# AT24-Timer-NEW.net
KiCad netlist of a schematic drawn in EAGLE
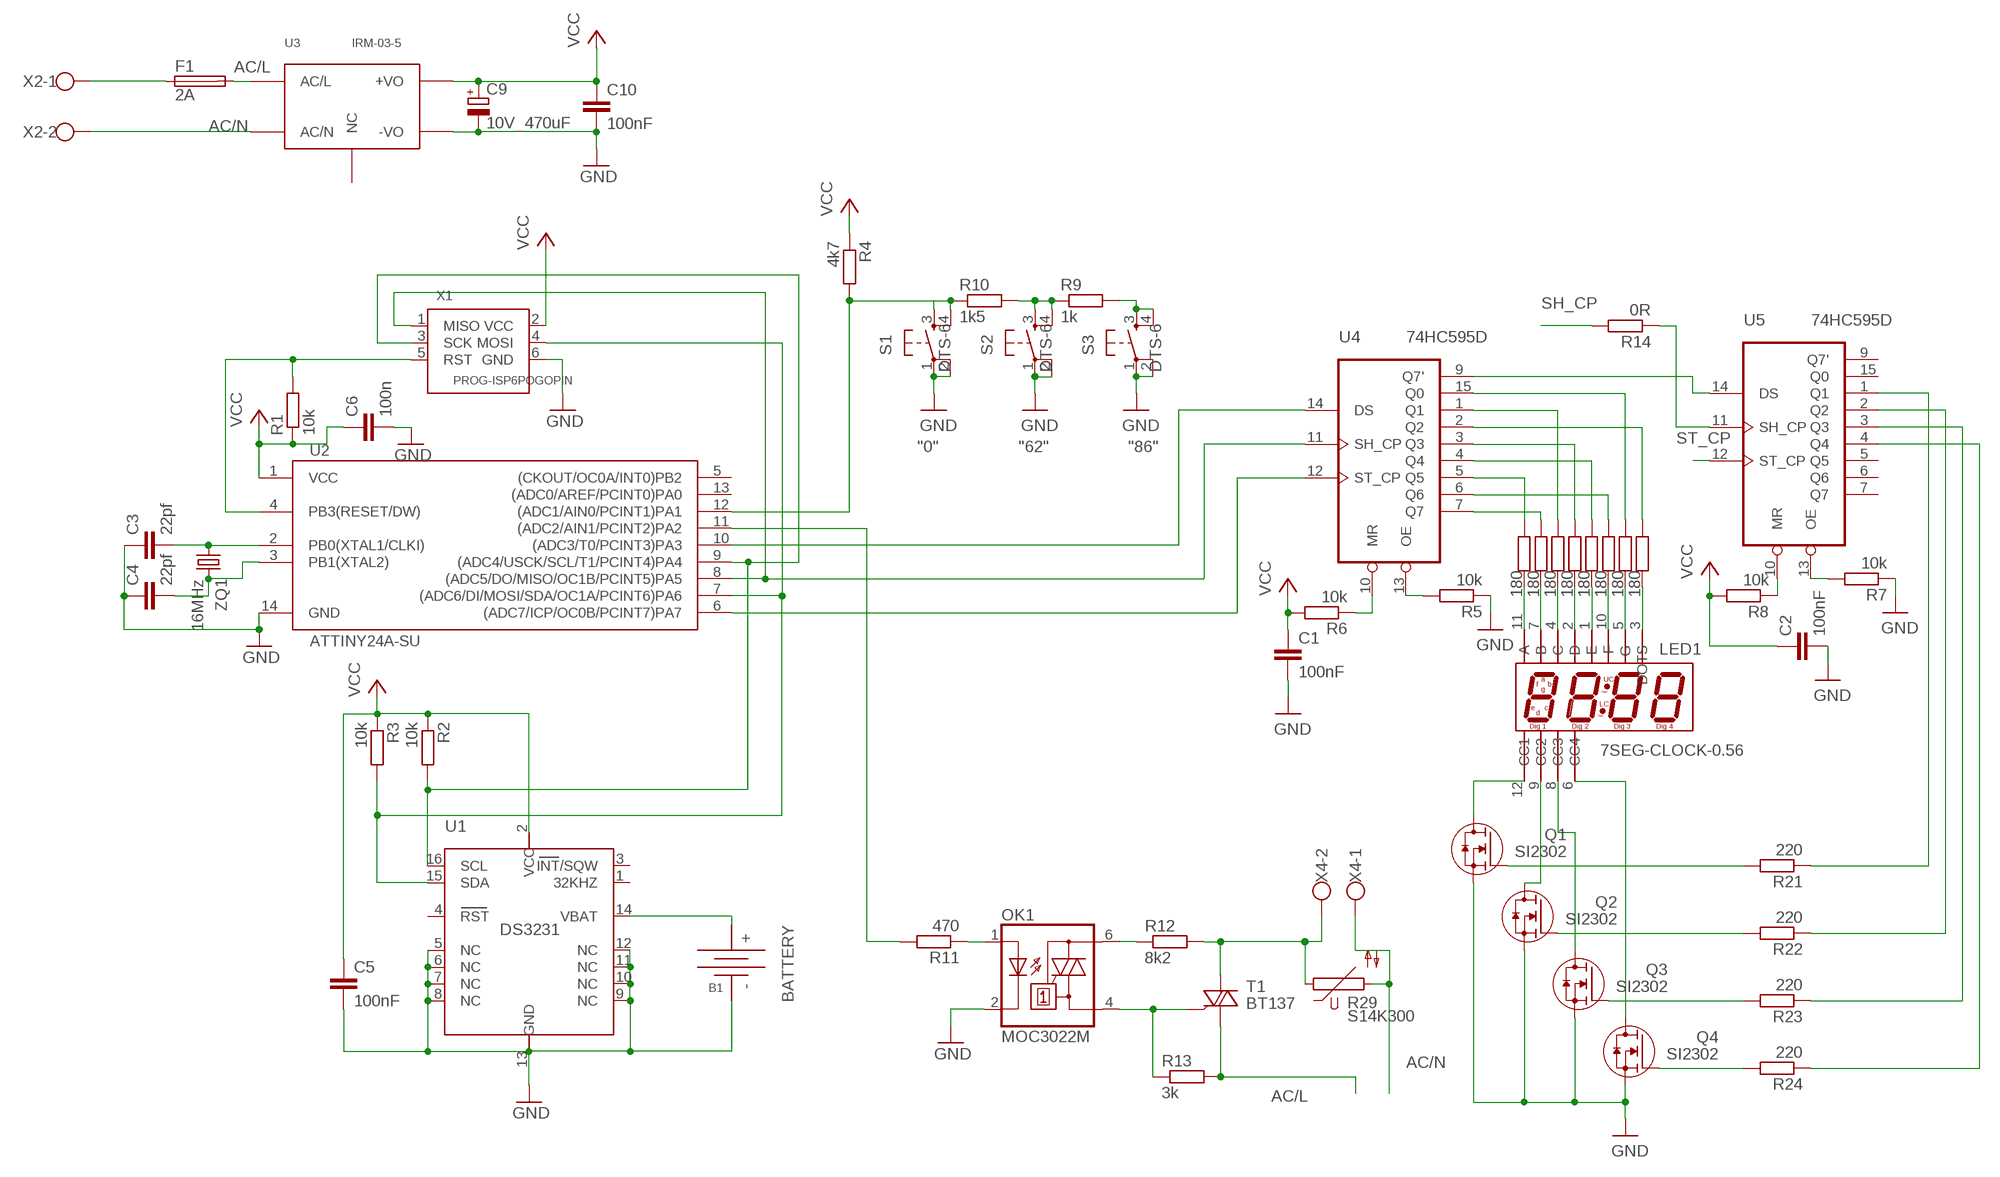
[diagram p0: schematic, sheet 1]

(export (version "E")
  (design (tool "Eeschema 10.0.6"))
  (components
    (comp (ref "B1")
      (value "BATTERY")
      (footprint "eagle-import:BTH2032-3")
      (libsource (lib "eagle-import") (part "BATTERY"))
    )
    (comp (ref "C1")
      (value "100nF")
      (footprint "eagle-import:C0603")
      (libsource (lib "eagle-import") (part "C-EUC0603"))
    )
    (comp (ref "C2")
      (value "100nF")
      (footprint "eagle-import:C0603")
      (libsource (lib "eagle-import") (part "C-EUC0603"))
    )
    (comp (ref "C3")
      (value "22pf")
      (footprint "eagle-import:C0603")
      (libsource (lib "eagle-import") (part "C-EUC0603"))
    )
    (comp (ref "C4")
      (value "22pf")
      (footprint "eagle-import:C0603")
      (libsource (lib "eagle-import") (part "C-EUC0603"))
    )
    (comp (ref "C5")
      (value "100nF")
      (footprint "eagle-import:C0603")
      (libsource (lib "eagle-import") (part "C-EUC0603"))
    )
    (comp (ref "C6")
      (value "100n")
      (footprint "eagle-import:C0603")
      (libsource (lib "eagle-import") (part "C-EUC0603"))
    )
    (comp (ref "C9")
      (value "10V_470uF")
      (footprint "eagle-import:D_7343-31W")
      (libsource (lib "eagle-import") (part "CPOL-EUD/7343-31W"))
    )
    (comp (ref "C10")
      (value "100nF")
      (footprint "eagle-import:C0805K")
      (libsource (lib "eagle-import") (part "C-EUC0805K"))
    )
    (comp (ref "F1")
      (value "2A")
      (footprint "eagle-import:SH22,5A")
      (fields (field (name "MPN") "0031.7701.11"))
      (libsource (lib "eagle-import") (part "SH22,5A"))
    )
    (comp (ref "LED1")
      (value "7SEG-CLOCK-0.56")
      (footprint "eagle-import:7SEG_4DIG_0.56")
      (libsource (lib "eagle-import") (part "7SEG-CLOCK-0.56"))
    )
    (comp (ref "OK1")
      (value "MOC3022M")
      (footprint "eagle-import:DIL06")
      (fields (field (name "MF") "FAIRCHILD SEMICONDUCTOR") (field (name "MPN") "MOC3022-M"))
      (libsource (lib "eagle-import") (part "MOC30M22"))
    )
    (comp (ref "Q1")
      (value "SI2302")
      (footprint "eagle-import:SOT-23-GSD")
      (libsource (lib "eagle-import") (part "SI2302"))
    )
    (comp (ref "Q2")
      (value "SI2302")
      (footprint "eagle-import:SOT-23-GSD")
      (libsource (lib "eagle-import") (part "SI2302"))
    )
    (comp (ref "Q3")
      (value "SI2302")
      (footprint "eagle-import:SOT-23-GSD")
      (libsource (lib "eagle-import") (part "SI2302"))
    )
    (comp (ref "Q4")
      (value "SI2302")
      (footprint "eagle-import:SOT-23-GSD")
      (libsource (lib "eagle-import") (part "SI2302"))
    )
    (comp (ref "R1")
      (value "10k")
      (footprint "eagle-import:R0805")
      (libsource (lib "eagle-import") (part "R-EU_R0805"))
    )
    (comp (ref "R2")
      (value "10k")
      (footprint "eagle-import:R0805")
      (libsource (lib "eagle-import") (part "R-EU_R0805"))
    )
    (comp (ref "R3")
      (value "10k")
      (footprint "eagle-import:R0805")
      (libsource (lib "eagle-import") (part "R-EU_R0805"))
    )
    (comp (ref "R4")
      (value "4k7")
      (footprint "eagle-import:R0805")
      (libsource (lib "eagle-import") (part "R-EU_R0805"))
    )
    (comp (ref "R5")
      (value "10k")
      (footprint "eagle-import:R0805")
      (libsource (lib "eagle-import") (part "R-EU_R0805"))
    )
    (comp (ref "R6")
      (value "10k")
      (footprint "eagle-import:R0805")
      (libsource (lib "eagle-import") (part "R-EU_R0805"))
    )
    (comp (ref "R7")
      (value "10k")
      (footprint "eagle-import:0805R")
      (libsource (lib "eagle-import") (part "R0805"))
    )
    (comp (ref "R8")
      (value "10k")
      (footprint "eagle-import:R0805")
      (libsource (lib "eagle-import") (part "R-EU_R0805"))
    )
    (comp (ref "R9")
      (value "1k")
      (footprint "eagle-import:R0805")
      (libsource (lib "eagle-import") (part "R-EU_R0805"))
    )
    (comp (ref "R10")
      (value "1k5")
      (footprint "eagle-import:R0805")
      (libsource (lib "eagle-import") (part "R-EU_R0805"))
    )
    (comp (ref "R11")
      (value "470")
      (footprint "eagle-import:R0805")
      (libsource (lib "eagle-import") (part "R-EU_R0805"))
    )
    (comp (ref "R12")
      (value "8k2")
      (footprint "eagle-import:0207_7")
      (libsource (lib "eagle-import") (part "R-EU_0207/7"))
    )
    (comp (ref "R13")
      (value "3k")
      (footprint "eagle-import:0207_7")
      (libsource (lib "eagle-import") (part "R-EU_0207/7"))
    )
    (comp (ref "R14")
      (value "0R")
      (footprint "eagle-import:0805R")
      (libsource (lib "eagle-import") (part "R0805"))
    )
    (comp (ref "R17")
      (value "180")
      (footprint "eagle-import:R0805")
      (libsource (lib "eagle-import") (part "R-EU_R0805"))
    )
    (comp (ref "R18")
      (value "180")
      (footprint "eagle-import:R0805")
      (libsource (lib "eagle-import") (part "R-EU_R0805"))
    )
    (comp (ref "R19")
      (value "180")
      (footprint "eagle-import:R0805")
      (libsource (lib "eagle-import") (part "R-EU_R0805"))
    )
    (comp (ref "R20")
      (value "180")
      (footprint "eagle-import:R0805")
      (libsource (lib "eagle-import") (part "R-EU_R0805"))
    )
    (comp (ref "R21")
      (value "220")
      (footprint "eagle-import:R0805")
      (libsource (lib "eagle-import") (part "R-EU_R0805"))
    )
    (comp (ref "R22")
      (value "220")
      (footprint "eagle-import:R0805")
      (libsource (lib "eagle-import") (part "R-EU_R0805"))
    )
    (comp (ref "R23")
      (value "220")
      (footprint "eagle-import:R0805")
      (libsource (lib "eagle-import") (part "R-EU_R0805"))
    )
    (comp (ref "R24")
      (value "220")
      (footprint "eagle-import:R0805")
      (libsource (lib "eagle-import") (part "R-EU_R0805"))
    )
    (comp (ref "R25")
      (value "180")
      (footprint "eagle-import:R0805")
      (libsource (lib "eagle-import") (part "R-EU_R0805"))
    )
    (comp (ref "R26")
      (value "180")
      (footprint "eagle-import:R0805")
      (libsource (lib "eagle-import") (part "R-EU_R0805"))
    )
    (comp (ref "R27")
      (value "180")
      (footprint "eagle-import:R0805")
      (libsource (lib "eagle-import") (part "R-EU_R0805"))
    )
    (comp (ref "R28")
      (value "180")
      (footprint "eagle-import:R0805")
      (libsource (lib "eagle-import") (part "R-EU_R0805"))
    )
    (comp (ref "R29")
      (value "S14K300")
      (footprint "eagle-import:S14K300")
      (libsource (lib "eagle-import") (part "S14K300"))
    )
    (comp (ref "S1")
      (value "DTS-6")
      (footprint "eagle-import:DTS-6")
      (libsource (lib "eagle-import") (part "DTS-6"))
    )
    (comp (ref "S2")
      (value "DTS-6")
      (footprint "eagle-import:DTS-6")
      (libsource (lib "eagle-import") (part "DTS-6"))
    )
    (comp (ref "S3")
      (value "DTS-6")
      (footprint "eagle-import:DTS-6")
      (libsource (lib "eagle-import") (part "DTS-6"))
    )
    (comp (ref "T1")
      (value "BT137")
      (footprint "eagle-import:TO220AB")
      (libsource (lib "eagle-import") (part "BT136"))
    )
    (comp (ref "U1")
      (value "DS3231")
      (footprint "eagle-import:SO16L")
      (libsource (lib "eagle-import") (part "DS3231"))
    )
    (comp (ref "U2")
      (value "ATTINY24A-SU")
      (footprint "eagle-import:SO14")
      (libsource (lib "eagle-import") (part "ATTINY24A-SU"))
    )
    (comp (ref "U3")
      (value "IRM-03-5")
      (footprint "eagle-import:IRM-03-_")
      (libsource (lib "eagle-import") (part "IRM-03-5"))
    )
    (comp (ref "U4")
      (value "74HC595D")
      (footprint "eagle-import:SO16")
      (libsource (lib "eagle-import") (part "74595DHC"))
    )
    (comp (ref "U5")
      (value "74HC595D")
      (footprint "eagle-import:SO16")
      (libsource (lib "eagle-import") (part "74595DHC"))
    )
    (comp (ref "X1")
      (value "PROG-ISP6POGOPIN")
      (footprint "eagle-import:PROG_POGOPIN")
      (libsource (lib "eagle-import") (part "PROG-ISP6POGOPIN"))
    )
    (comp (ref "X2")
      (value "W237-102")
      (footprint "eagle-import:W237-102")
      (fields (field (name "MPN") "237-102"))
      (libsource (lib "eagle-import") (part "W237-102"))
    )
    (comp (ref "X4")
      (value "W237-102")
      (footprint "eagle-import:W237-102")
      (fields (field (name "MPN") "237-102"))
      (libsource (lib "eagle-import") (part "W237-102"))
    )
    (comp (ref "ZQ1")
      (value "16MHz")
      (footprint "eagle-import:HC49_S")
      (libsource (lib "eagle-import") (part "CRYSTALHC49S"))
    )
  )
  (nets
    (net (code "1") (name "/AC{slash}L") (class "Default")
      (node (ref "F1") (pin "2") (pinfunction "2_2") (pintype "passive"))
      (node (ref "R13") (pin "2") (pinfunction "2_2") (pintype "passive"))
      (node (ref "T1") (pin "1") (pinfunction "A1_1") (pintype "passive"))
      (node (ref "U3") (pin "P$1") (pinfunction "AC/L_P$1") (pintype "power_in"))
    )
    (net (code "2") (name "/AC{slash}N") (class "Default")
      (node (ref "R29") (pin "2") (pinfunction "2_2") (pintype "passive"))
      (node (ref "U3") (pin "P$2") (pinfunction "AC/N_P$2") (pintype "power_in"))
      (node (ref "X2") (pin "2") (pinfunction "KL_2") (pintype "passive"))
      (node (ref "X4") (pin "1") (pinfunction "KL_1") (pintype "passive"))
    )
    (net (code "3") (name "/NC") (class "Default")
      (node (ref "U3") (pin "P$3") (pinfunction "NC_P$3") (pintype "power_in"))
    )
    (net (code "4") (name "/SH_CP") (class "Default")
      (node (ref "R14") (pin "2") (pinfunction "2_2") (pintype "passive"))
      (node (ref "U2") (pin "8") (pinfunction "(ADC5/DO/MISO/OC1B/PCINT5)PA5_8") (pintype "bidirectional"))
      (node (ref "U4") (pin "11") (pinfunction "SH_CP_11") (pintype "input"))
      (node (ref "X1") (pin "1") (pinfunction "MISO_1") (pintype "bidirectional"))
    )
    (net (code "5") (name "/ST_CP") (class "Default")
      (node (ref "U2") (pin "6") (pinfunction "(ADC7/ICP/OC0B/PCINT7)PA7_6") (pintype "bidirectional"))
      (node (ref "U4") (pin "12") (pinfunction "ST_CP_12") (pintype "input"))
      (node (ref "U5") (pin "12") (pinfunction "ST_CP_12") (pintype "input"))
    )
    (net (code "6") (name "GND") (class "Default")
      (node (ref "B1") (pin "-") (pinfunction "-_-") (pintype "power_in"))
      (node (ref "C1") (pin "2") (pinfunction "2_2") (pintype "passive"))
      (node (ref "C10") (pin "2") (pinfunction "2_2") (pintype "passive"))
      (node (ref "C2") (pin "2") (pinfunction "2_2") (pintype "passive"))
      (node (ref "C3") (pin "1") (pinfunction "1_1") (pintype "passive"))
      (node (ref "C4") (pin "1") (pinfunction "1_1") (pintype "passive"))
      (node (ref "C5") (pin "2") (pinfunction "2_2") (pintype "passive"))
      (node (ref "C6") (pin "2") (pinfunction "2_2") (pintype "passive"))
      (node (ref "C9") (pin "-") (pinfunction "-_-") (pintype "passive"))
      (node (ref "OK1") (pin "2") (pinfunction "C_2") (pintype "passive"))
      (node (ref "Q1") (pin "S") (pinfunction "S_S") (pintype "passive"))
      (node (ref "Q2") (pin "S") (pinfunction "S_S") (pintype "passive"))
      (node (ref "Q3") (pin "S") (pinfunction "S_S") (pintype "passive"))
      (node (ref "Q4") (pin "S") (pinfunction "S_S") (pintype "passive"))
      (node (ref "R5") (pin "1") (pinfunction "1_1") (pintype "passive"))
      (node (ref "R7") (pin "1") (pinfunction "1_1") (pintype "passive"))
      (node (ref "S1") (pin "1") (pinfunction "1_1") (pintype "passive"))
      (node (ref "S1") (pin "2") (pinfunction "2_2") (pintype "passive"))
      (node (ref "S2") (pin "1") (pinfunction "1_1") (pintype "passive"))
      (node (ref "S2") (pin "2") (pinfunction "2_2") (pintype "passive"))
      (node (ref "S3") (pin "1") (pinfunction "1_1") (pintype "passive"))
      (node (ref "S3") (pin "2") (pinfunction "2_2") (pintype "passive"))
      (node (ref "U1") (pin "10") (pinfunction "NC_10") (pintype "bidirectional"))
      (node (ref "U1") (pin "11") (pinfunction "NC_11") (pintype "bidirectional"))
      (node (ref "U1") (pin "12") (pinfunction "NC_12") (pintype "bidirectional"))
      (node (ref "U1") (pin "13") (pinfunction "GND_13") (pintype "power_in"))
      (node (ref "U1") (pin "5") (pinfunction "NC_5") (pintype "bidirectional"))
      (node (ref "U1") (pin "6") (pinfunction "NC_6") (pintype "bidirectional"))
      (node (ref "U1") (pin "7") (pinfunction "NC_7") (pintype "bidirectional"))
      (node (ref "U1") (pin "8") (pinfunction "NC_8") (pintype "bidirectional"))
      (node (ref "U1") (pin "9") (pinfunction "NC_9") (pintype "bidirectional"))
      (node (ref "U2") (pin "14") (pinfunction "GND_14") (pintype "power_in"))
      (node (ref "U3") (pin "P$4") (pinfunction "-VO_P$4") (pintype "power_in"))
      (node (ref "X1") (pin "6") (pinfunction "GND_6") (pintype "power_in"))
    )
    (net (code "7") (name "Net-(LED1-A)") (class "Default")
      (node (ref "LED1") (pin "11") (pinfunction "A_11") (pintype "input"))
      (node (ref "R17") (pin "2") (pinfunction "2_2") (pintype "passive"))
    )
    (net (code "8") (name "Net-(LED1-B)") (class "Default")
      (node (ref "LED1") (pin "7") (pinfunction "B_7") (pintype "input"))
      (node (ref "R18") (pin "2") (pinfunction "2_2") (pintype "passive"))
    )
    (net (code "9") (name "Net-(LED1-C)") (class "Default")
      (node (ref "LED1") (pin "4") (pinfunction "C_4") (pintype "input"))
      (node (ref "R19") (pin "2") (pinfunction "2_2") (pintype "passive"))
    )
    (net (code "10") (name "Net-(LED1-CC1)") (class "Default")
      (node (ref "LED1") (pin "12") (pinfunction "CC1_12") (pintype "input"))
      (node (ref "Q1") (pin "D") (pinfunction "D_D") (pintype "passive"))
    )
    (net (code "11") (name "Net-(LED1-CC2)") (class "Default")
      (node (ref "LED1") (pin "9") (pinfunction "CC2_9") (pintype "input"))
      (node (ref "Q2") (pin "D") (pinfunction "D_D") (pintype "passive"))
    )
    (net (code "12") (name "Net-(LED1-CC3)") (class "Default")
      (node (ref "LED1") (pin "8") (pinfunction "CC3_8") (pintype "input"))
      (node (ref "Q3") (pin "D") (pinfunction "D_D") (pintype "passive"))
    )
    (net (code "13") (name "Net-(LED1-CC4)") (class "Default")
      (node (ref "LED1") (pin "6") (pinfunction "CC4_6") (pintype "input"))
      (node (ref "Q4") (pin "D") (pinfunction "D_D") (pintype "passive"))
    )
    (net (code "14") (name "Net-(LED1-D)") (class "Default")
      (node (ref "LED1") (pin "2") (pinfunction "D_2") (pintype "input"))
      (node (ref "R20") (pin "2") (pinfunction "2_2") (pintype "passive"))
    )
    (net (code "15") (name "Net-(LED1-DOTS)") (class "Default")
      (node (ref "LED1") (pin "3") (pinfunction "DOTS_3") (pintype "input"))
      (node (ref "R28") (pin "2") (pinfunction "2_2") (pintype "passive"))
    )
    (net (code "16") (name "Net-(LED1-E)") (class "Default")
      (node (ref "LED1") (pin "1") (pinfunction "E_1") (pintype "input"))
      (node (ref "R25") (pin "2") (pinfunction "2_2") (pintype "passive"))
    )
    (net (code "17") (name "Net-(LED1-F)") (class "Default")
      (node (ref "LED1") (pin "10") (pinfunction "F_10") (pintype "input"))
      (node (ref "R26") (pin "2") (pinfunction "2_2") (pintype "passive"))
    )
    (net (code "18") (name "Net-(LED1-G)") (class "Default")
      (node (ref "LED1") (pin "5") (pinfunction "G_5") (pintype "input"))
      (node (ref "R27") (pin "2") (pinfunction "2_2") (pintype "passive"))
    )
    (net (code "19") (name "Net-(OK1-A)") (class "Default")
      (node (ref "OK1") (pin "1") (pinfunction "A_1") (pintype "passive"))
      (node (ref "R11") (pin "1") (pinfunction "1_1") (pintype "passive"))
    )
    (net (code "20") (name "Net-(OK1-A1)") (class "Default")
      (node (ref "OK1") (pin "4") (pinfunction "A1_4") (pintype "passive"))
      (node (ref "R13") (pin "1") (pinfunction "1_1") (pintype "passive"))
      (node (ref "T1") (pin "3") (pinfunction "G_3") (pintype "passive"))
    )
    (net (code "21") (name "Net-(OK1-A2)") (class "Default")
      (node (ref "OK1") (pin "6") (pinfunction "A2_6") (pintype "passive"))
      (node (ref "R12") (pin "1") (pinfunction "1_1") (pintype "passive"))
    )
    (net (code "22") (name "Net-(Q1-PadG)") (class "Default")
      (node (ref "Q1") (pin "G") (pinfunction "G_G") (pintype "passive"))
      (node (ref "R21") (pin "2") (pinfunction "2_2") (pintype "passive"))
    )
    (net (code "23") (name "Net-(Q2-PadG)") (class "Default")
      (node (ref "Q2") (pin "G") (pinfunction "G_G") (pintype "passive"))
      (node (ref "R22") (pin "2") (pinfunction "2_2") (pintype "passive"))
    )
    (net (code "24") (name "Net-(Q3-PadG)") (class "Default")
      (node (ref "Q3") (pin "G") (pinfunction "G_G") (pintype "passive"))
      (node (ref "R23") (pin "2") (pinfunction "2_2") (pintype "passive"))
    )
    (net (code "25") (name "Net-(Q4-PadG)") (class "Default")
      (node (ref "Q4") (pin "G") (pinfunction "G_G") (pintype "passive"))
      (node (ref "R24") (pin "2") (pinfunction "2_2") (pintype "passive"))
    )
    (net (code "26") (name "Net-(R9-Pad1)") (class "Default")
      (node (ref "R9") (pin "1") (pinfunction "1_1") (pintype "passive"))
      (node (ref "S3") (pin "3") (pinfunction "3_3") (pintype "passive"))
      (node (ref "S3") (pin "4") (pinfunction "4_4") (pintype "passive"))
    )
    (net (code "27") (name "Net-(R10-Pad2)") (class "Default")
      (node (ref "R10") (pin "2") (pinfunction "2_2") (pintype "passive"))
      (node (ref "R9") (pin "2") (pinfunction "2_2") (pintype "passive"))
      (node (ref "S2") (pin "3") (pinfunction "3_3") (pintype "passive"))
      (node (ref "S2") (pin "4") (pinfunction "4_4") (pintype "passive"))
    )
    (net (code "28") (name "Net-(T1-A2)") (class "Default")
      (node (ref "R12") (pin "2") (pinfunction "2_2") (pintype "passive"))
      (node (ref "R29") (pin "1") (pinfunction "1_1") (pintype "passive"))
      (node (ref "T1") (pin "2") (pinfunction "A2_2") (pintype "passive"))
      (node (ref "X4") (pin "2") (pinfunction "KL_2") (pintype "passive"))
    )
    (net (code "29") (name "Net-(U1-SCL)") (class "Default")
      (node (ref "R2") (pin "2") (pinfunction "2_2") (pintype "passive"))
      (node (ref "U1") (pin "16") (pinfunction "SCL_16") (pintype "bidirectional"))
      (node (ref "U2") (pin "9") (pinfunction "(ADC4/USCK/SCL/T1/PCINT4)PA4_9") (pintype "bidirectional"))
      (node (ref "X1") (pin "3") (pinfunction "SCK_3") (pintype "bidirectional"))
    )
    (net (code "30") (name "Net-(U1-SDA)") (class "Default")
      (node (ref "R3") (pin "2") (pinfunction "2_2") (pintype "passive"))
      (node (ref "U1") (pin "15") (pinfunction "SDA_15") (pintype "bidirectional"))
      (node (ref "U2") (pin "7") (pinfunction "(ADC6/DI/MOSI/SDA/OC1A/PCINT6)PA6_7") (pintype "bidirectional"))
      (node (ref "X1") (pin "4") (pinfunction "MOSI_4") (pintype "bidirectional"))
    )
    (net (code "31") (name "Net-(U1-VBAT)") (class "Default")
      (node (ref "B1") (pin "+") (pinfunction "+_+") (pintype "power_in"))
      (node (ref "U1") (pin "14") (pinfunction "VBAT_14") (pintype "bidirectional"))
    )
    (net (code "32") (name "Net-(U2-(ADC1{slash}AIN0{slash}PCINT1)PA1)") (class "Default")
      (node (ref "R10") (pin "1") (pinfunction "1_1") (pintype "passive"))
      (node (ref "R4") (pin "2") (pinfunction "2_2") (pintype "passive"))
      (node (ref "S1") (pin "3") (pinfunction "3_3") (pintype "passive"))
      (node (ref "S1") (pin "4") (pinfunction "4_4") (pintype "passive"))
      (node (ref "U2") (pin "12") (pinfunction "(ADC1/AIN0/PCINT1)PA1_12") (pintype "bidirectional"))
    )
    (net (code "33") (name "Net-(U2-(ADC2{slash}AIN1{slash}PCINT2)PA2)") (class "Default")
      (node (ref "R11") (pin "2") (pinfunction "2_2") (pintype "passive"))
      (node (ref "U2") (pin "11") (pinfunction "(ADC2/AIN1/PCINT2)PA2_11") (pintype "bidirectional"))
    )
    (net (code "34") (name "Net-(U2-(ADC3{slash}T0{slash}PCINT3)PA3)") (class "Default")
      (node (ref "U2") (pin "10") (pinfunction "(ADC3/T0/PCINT3)PA3_10") (pintype "bidirectional"))
      (node (ref "U4") (pin "14") (pinfunction "DS_14") (pintype "input"))
    )
    (net (code "35") (name "Net-(U2-PB0(XTAL1{slash}CLKI))") (class "Default")
      (node (ref "C3") (pin "2") (pinfunction "2_2") (pintype "passive"))
      (node (ref "U2") (pin "2") (pinfunction "PB0(XTAL1/CLKI)_2") (pintype "bidirectional"))
      (node (ref "ZQ1") (pin "1") (pinfunction "1_1") (pintype "passive"))
    )
    (net (code "36") (name "Net-(U2-PB1(XTAL2))") (class "Default")
      (node (ref "C4") (pin "2") (pinfunction "2_2") (pintype "passive"))
      (node (ref "U2") (pin "3") (pinfunction "PB1(XTAL2)_3") (pintype "bidirectional"))
      (node (ref "ZQ1") (pin "2") (pinfunction "2_2") (pintype "passive"))
    )
    (net (code "37") (name "Net-(U2-PB3(RESET{slash}DW))") (class "Default")
      (node (ref "R1") (pin "2") (pinfunction "2_2") (pintype "passive"))
      (node (ref "U2") (pin "4") (pinfunction "PB3(RESET/DW)_4") (pintype "bidirectional"))
      (node (ref "X1") (pin "5") (pinfunction "RST_5") (pintype "bidirectional"))
    )
    (net (code "38") (name "Net-(U4A-MR)") (class "Default")
      (node (ref "R6") (pin "1") (pinfunction "1_1") (pintype "passive"))
      (node (ref "U4") (pin "10") (pinfunction "MR_10") (pintype "input"))
    )
    (net (code "39") (name "Net-(U4A-OE)") (class "Default")
      (node (ref "R5") (pin "2") (pinfunction "2_2") (pintype "passive"))
      (node (ref "U4") (pin "13") (pinfunction "OE_13") (pintype "input"))
    )
    (net (code "40") (name "Net-(U4A-Q0)") (class "Default")
      (node (ref "R27") (pin "1") (pinfunction "1_1") (pintype "passive"))
      (node (ref "U4") (pin "15") (pinfunction "Q0_15") (pintype "output"))
    )
    (net (code "41") (name "Net-(U4A-Q1)") (class "Default")
      (node (ref "R19") (pin "1") (pinfunction "1_1") (pintype "passive"))
      (node (ref "U4") (pin "1") (pinfunction "Q1_1") (pintype "output"))
    )
    (net (code "42") (name "Net-(U4A-Q2)") (class "Default")
      (node (ref "R28") (pin "1") (pinfunction "1_1") (pintype "passive"))
      (node (ref "U4") (pin "2") (pinfunction "Q2_2") (pintype "output"))
    )
    (net (code "43") (name "Net-(U4A-Q3)") (class "Default")
      (node (ref "R20") (pin "1") (pinfunction "1_1") (pintype "passive"))
      (node (ref "U4") (pin "3") (pinfunction "Q3_3") (pintype "output"))
    )
    (net (code "44") (name "Net-(U4A-Q4)") (class "Default")
      (node (ref "R25") (pin "1") (pinfunction "1_1") (pintype "passive"))
      (node (ref "U4") (pin "4") (pinfunction "Q4_4") (pintype "output"))
    )
    (net (code "45") (name "Net-(U4A-Q5)") (class "Default")
      (node (ref "R17") (pin "1") (pinfunction "1_1") (pintype "passive"))
      (node (ref "U4") (pin "5") (pinfunction "Q5_5") (pintype "output"))
    )
    (net (code "46") (name "Net-(U4A-Q6)") (class "Default")
      (node (ref "R26") (pin "1") (pinfunction "1_1") (pintype "passive"))
      (node (ref "U4") (pin "6") (pinfunction "Q6_6") (pintype "output"))
    )
    (net (code "47") (name "Net-(U4A-Q7')") (class "Default")
      (node (ref "U4") (pin "9") (pinfunction "Q7'_9") (pintype "output"))
      (node (ref "U5") (pin "14") (pinfunction "DS_14") (pintype "input"))
    )
    (net (code "48") (name "Net-(U4A-Q7)") (class "Default")
      (node (ref "R18") (pin "1") (pinfunction "1_1") (pintype "passive"))
      (node (ref "U4") (pin "7") (pinfunction "Q7_7") (pintype "output"))
    )
    (net (code "49") (name "Net-(U5A-MR)") (class "Default")
      (node (ref "R8") (pin "1") (pinfunction "1_1") (pintype "passive"))
      (node (ref "U5") (pin "10") (pinfunction "MR_10") (pintype "input"))
    )
    (net (code "50") (name "Net-(U5A-OE)") (class "Default")
      (node (ref "R7") (pin "2") (pinfunction "2_2") (pintype "passive"))
      (node (ref "U5") (pin "13") (pinfunction "OE_13") (pintype "input"))
    )
    (net (code "51") (name "Net-(U5A-Q1)") (class "Default")
      (node (ref "R21") (pin "1") (pinfunction "1_1") (pintype "passive"))
      (node (ref "U5") (pin "1") (pinfunction "Q1_1") (pintype "output"))
    )
    (net (code "52") (name "Net-(U5A-Q2)") (class "Default")
      (node (ref "R22") (pin "1") (pinfunction "1_1") (pintype "passive"))
      (node (ref "U5") (pin "2") (pinfunction "Q2_2") (pintype "output"))
    )
    (net (code "53") (name "Net-(U5A-Q3)") (class "Default")
      (node (ref "R23") (pin "1") (pinfunction "1_1") (pintype "passive"))
      (node (ref "U5") (pin "3") (pinfunction "Q3_3") (pintype "output"))
    )
    (net (code "54") (name "Net-(U5A-Q4)") (class "Default")
      (node (ref "R24") (pin "1") (pinfunction "1_1") (pintype "passive"))
      (node (ref "U5") (pin "4") (pinfunction "Q4_4") (pintype "output"))
    )
    (net (code "55") (name "Net-(U5A-SH_CP)") (class "Default")
      (node (ref "R14") (pin "1") (pinfunction "1_1") (pintype "passive"))
      (node (ref "U5") (pin "11") (pinfunction "SH_CP_11") (pintype "input"))
    )
    (net (code "56") (name "Net-(X2A-KL)") (class "Default")
      (node (ref "F1") (pin "1") (pinfunction "1_1") (pintype "passive"))
      (node (ref "X2") (pin "1") (pinfunction "KL_1") (pintype "passive"))
    )
    (net (code "57") (name "VCC") (class "Default")
      (node (ref "C1") (pin "1") (pinfunction "1_1") (pintype "passive"))
      (node (ref "C10") (pin "1") (pinfunction "1_1") (pintype "passive"))
      (node (ref "C2") (pin "1") (pinfunction "1_1") (pintype "passive"))
      (node (ref "C5") (pin "1") (pinfunction "1_1") (pintype "passive"))
      (node (ref "C6") (pin "1") (pinfunction "1_1") (pintype "passive"))
      (node (ref "C9") (pin "+") (pinfunction "+_+") (pintype "passive"))
      (node (ref "R1") (pin "1") (pinfunction "1_1") (pintype "passive"))
      (node (ref "R2") (pin "1") (pinfunction "1_1") (pintype "passive"))
      (node (ref "R3") (pin "1") (pinfunction "1_1") (pintype "passive"))
      (node (ref "R4") (pin "1") (pinfunction "1_1") (pintype "passive"))
      (node (ref "R6") (pin "2") (pinfunction "2_2") (pintype "passive"))
      (node (ref "R8") (pin "2") (pinfunction "2_2") (pintype "passive"))
      (node (ref "U1") (pin "2") (pinfunction "VCC_2") (pintype "power_in"))
      (node (ref "U2") (pin "1") (pinfunction "VCC_1") (pintype "power_in"))
      (node (ref "U3") (pin "P$5") (pinfunction "+VO_P$5") (pintype "power_in"))
      (node (ref "X1") (pin "2") (pinfunction "VCC_2") (pintype "bidirectional"))
    )
    (net (code "58") (name "unconnected-(U1-32KHZ-Pad1)") (class "Default")
      (node (ref "U1") (pin "1") (pinfunction "32KHZ_1") (pintype "bidirectional"))
    )
    (net (code "59") (name "unconnected-(U1-INT{slash}SQW-Pad3)") (class "Default")
      (node (ref "U1") (pin "3") (pinfunction "INT/SQW_3") (pintype "bidirectional"))
    )
    (net (code "60") (name "unconnected-(U1-RST-Pad4)") (class "Default")
      (node (ref "U1") (pin "4") (pinfunction "RST_4") (pintype "bidirectional"))
    )
    (net (code "61") (name "unconnected-(U2-(ADC0{slash}AREF{slash}PCINT0)PA0-Pad13)") (class "Default")
      (node (ref "U2") (pin "13") (pinfunction "(ADC0/AREF/PCINT0)PA0_13") (pintype "bidirectional"))
    )
    (net (code "62") (name "unconnected-(U2-(CKOUT{slash}OC0A{slash}INT0)PB2-Pad5)") (class "Default")
      (node (ref "U2") (pin "5") (pinfunction "(CKOUT/OC0A/INT0)PB2_5") (pintype "bidirectional"))
    )
    (net (code "63") (name "unconnected-(U5A-Q0-Pad15)") (class "Default")
      (node (ref "U5") (pin "15") (pinfunction "Q0_15") (pintype "output"))
    )
    (net (code "64") (name "unconnected-(U5A-Q5-Pad5)") (class "Default")
      (node (ref "U5") (pin "5") (pinfunction "Q5_5") (pintype "output"))
    )
    (net (code "65") (name "unconnected-(U5A-Q6-Pad6)") (class "Default")
      (node (ref "U5") (pin "6") (pinfunction "Q6_6") (pintype "output"))
    )
    (net (code "66") (name "unconnected-(U5A-Q7'-Pad9)") (class "Default")
      (node (ref "U5") (pin "9") (pinfunction "Q7'_9") (pintype "output"))
    )
    (net (code "67") (name "unconnected-(U5A-Q7-Pad7)") (class "Default")
      (node (ref "U5") (pin "7") (pinfunction "Q7_7") (pintype "output"))
    )
  )
)
